# DC-DC_24V_To_5V0.net
KiCad netlist of a schematic drawn in Altium Designer
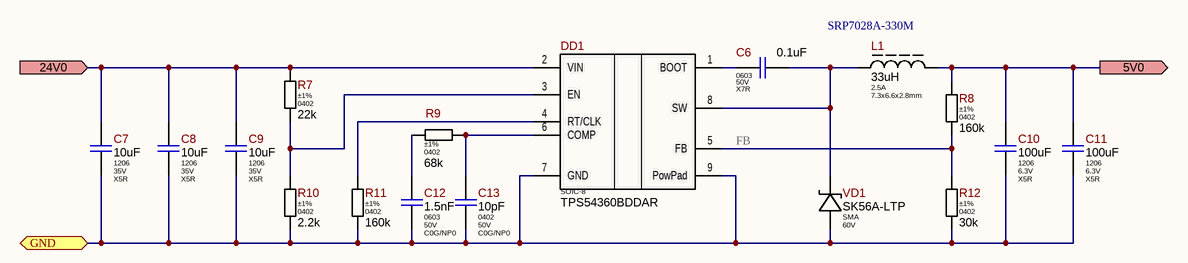
[diagram p0: DC-DC_24V_To_5V0.SchDoc]

(export (version "E")
  (design (tool "Eeschema 10.0.6"))
  (components
    (comp (ref "C6")
      (value "0.1uF")
      (footprint "C_CERAMIC_0603_MED")
      (description "100nF 50V X7R ±10% 0603 Ceramic Capacitor RoHS")
      (fields
        (field (name "PACKAGE") "0603")
        (field (name "VOLTAGE") "50V")
        (field (name "DIELECTRIC TYPE") "X7R")
        (field (name "PART NUMBER") "CL10B104KB8NNNC")
        (field (name "MANUFACTURER") "Samsung Electro-Mechanics")
      )
      (libsource (lib "EL.XXX.T01") (part "Capacitor-NonPolar"))
    )
    (comp (ref "C7")
      (value "10uF")
      (footprint "CAP-1206(3216)X85T15")
      (description "10uF 35V X5R ±10% 1206 Ceramic Capacitor RoHS")
      (fields
        (field (name "PACKAGE") "1206")
        (field (name "VOLTAGE") "35V")
        (field (name "DIELECTRIC TYPE") "X5R")
        (field (name "PART NUMBER") "GRM319R6YA106KA12D")
        (field (name "MANUFACTURER") "Murata Electronics")
      )
      (libsource (lib "EL.XXX.T01") (part "Capacitor-NonPolar"))
    )
    (comp (ref "C8")
      (value "10uF")
      (footprint "CAP-1206(3216)X85T15")
      (description "10uF 35V X5R ±10% 1206 Ceramic Capacitor RoHS")
      (fields
        (field (name "PACKAGE") "1206")
        (field (name "VOLTAGE") "35V")
        (field (name "DIELECTRIC TYPE") "X5R")
        (field (name "PART NUMBER") "GRM319R6YA106KA12D")
        (field (name "MANUFACTURER") "Murata Electronics")
      )
      (libsource (lib "EL.XXX.T01") (part "Capacitor-NonPolar"))
    )
    (comp (ref "C9")
      (value "10uF")
      (footprint "CAP-1206(3216)X85T15")
      (description "10uF 35V X5R ±10% 1206 Ceramic Capacitor RoHS")
      (fields
        (field (name "PACKAGE") "1206")
        (field (name "VOLTAGE") "35V")
        (field (name "DIELECTRIC TYPE") "X5R")
        (field (name "PART NUMBER") "GRM319R6YA106KA12D")
        (field (name "MANUFACTURER") "Murata Electronics")
      )
      (libsource (lib "EL.XXX.T01") (part "Capacitor-NonPolar"))
    )
    (comp (ref "C10")
      (value "100uF")
      (footprint "C_CERAMIC_1206_MED")
      (description "100uF 6.3V X5R ±20% 1206 Ceramic Capacitor RoHS")
      (fields
        (field (name "PACKAGE") "1206")
        (field (name "VOLTAGE") "6.3V")
        (field (name "DIELECTRIC TYPE") "X5R")
        (field (name "PART NUMBER") "CL31A107MQHNNNE")
        (field (name "MANUFACTURER") "Samsung Electro-Mechanics")
      )
      (libsource (lib "EL.XXX.T01") (part "Capacitor-NonPolar"))
    )
    (comp (ref "C11")
      (value "100uF")
      (footprint "C_CERAMIC_1206_MED")
      (description "100uF 6.3V X5R ±20% 1206 Ceramic Capacitor RoHS")
      (fields
        (field (name "PACKAGE") "1206")
        (field (name "VOLTAGE") "6.3V")
        (field (name "DIELECTRIC TYPE") "X5R")
        (field (name "PART NUMBER") "CL31A107MQHNNNE")
        (field (name "MANUFACTURER") "Samsung Electro-Mechanics")
      )
      (libsource (lib "EL.XXX.T01") (part "Capacitor-NonPolar"))
    )
    (comp (ref "C12")
      (value "1.5nF")
      (footprint "C_CERAMIC_0603_MED")
      (description "1.5nF 50V C0G(NP0) ±5% 0603 Ceramic Capacitor RoHS")
      (fields
        (field (name "PACKAGE") "0603")
        (field (name "VOLTAGE") "50V")
        (field (name "DIELECTRIC TYPE") "C0G/NP0")
        (field (name "PART NUMBER") "GRM1885C1H152JA01D")
        (field (name "MANUFACTURER") "Murata Electronics")
      )
      (libsource (lib "EL.XXX.T01") (part "Capacitor-NonPolar"))
    )
    (comp (ref "C13")
      (value "10pF")
      (footprint "C_CERAMIC_0402_MED")
      (description "10pF 50V C0G ±5% 0402 Ceramic Capacitor RoHS")
      (fields
        (field (name "PACKAGE") "0402")
        (field (name "VOLTAGE") "50V")
        (field (name "DIELECTRIC TYPE") "C0G/NP0")
        (field (name "PART NUMBER") "CL05C100JB5NNNC")
        (field (name "MANUFACTURER") "Samsung Electro-Mechanics")
      )
      (libsource (lib "EL.XXX.T01") (part "Capacitor-NonPolar"))
    )
    (comp (ref "DD1")
      (value "TPS54360BDDAR")
      (footprint "SOIC127P620X170_HS-9N")
      (description "60V Input, 3.5A, Step-Down DC/DC Converter With Eco-Mode, SOIC-8 EP")
      (fields
        (field (name "PACKAGE") "SOIC-8")
        (field (name "PART NUMBER") "TPS54360BDDAR")
        (field (name "MANUFACTURER") "Texas Instruments")
      )
      (libsource (lib "EL.XXX.T01") (part "TPS54360B"))
    )
    (comp (ref "L1")
      (value "33uH")
      (footprint "SRP7028A-Series")
      (description "33uH Shielded Wirewound Power Inductor 2.5A 240mOhm Max")
      (fields
        (field (name "CURRENT") "2.5A")
        (field (name "PACKAGE") "7.3x6.6x2.8mm")
        (field (name "PART NUMBER") "SRP7028A-330M")
        (field (name "TOLERANCE") "±20%")
        (field (name "MANUFACTURER") "Bourns Inc")
      )
      (libsource (lib "EL.XXX.T01") (part "Inductor-Ferrite-Fixed"))
    )
    (comp (ref "R7")
      (value "22k")
      (footprint "R_ANY_CHIP_0402_MED")
      (description "22 kOhms ±1% 1/16W 0402 Thick Film Resistor")
      (fields
        (field (name "TOLERANCE") "±1%")
        (field (name "PACKAGE") "0402")
        (field (name "PART NUMBER") "RC0402FR-0722KL")
        (field (name "MANUFACTURER") "Yageo")
      )
      (libsource (lib "EL.XXX.T01") (part "Resistor"))
    )
    (comp (ref "R8")
      (value "160k")
      (footprint "R_ANY_CHIP_0402_MED")
      (description "160 kOhms ±1% 1/16W 0402 Thick Film Resistor")
      (fields
        (field (name "TOLERANCE") "±1%")
        (field (name "PACKAGE") "0402")
        (field (name "PART NUMBER") "RC0402FR-07160KL")
        (field (name "MANUFACTURER") "Yageo")
      )
      (libsource (lib "EL.XXX.T01") (part "Resistor"))
    )
    (comp (ref "R9")
      (value "68k")
      (footprint "R_ANY_CHIP_0402_MED")
      (description "68 kOhms ±1% 1/16W 0402 Thick Film Resistor")
      (fields
        (field (name "TOLERANCE") "±1%")
        (field (name "PACKAGE") "0402")
        (field (name "PART NUMBER") "RC0402FR-0768KL")
        (field (name "MANUFACTURER") "Yageo")
      )
      (libsource (lib "EL.XXX.T01") (part "Resistor"))
    )
    (comp (ref "R10")
      (value "2.2k")
      (footprint "R_ANY_CHIP_0402_MED")
      (description "2.2 kOhms ±1% 1/16W 0402 Thick Film Resistor")
      (fields
        (field (name "TOLERANCE") "±1%")
        (field (name "PACKAGE") "0402")
        (field (name "PART NUMBER") "RC0402FR-072K2L")
        (field (name "MANUFACTURER") "Yageo")
      )
      (libsource (lib "EL.XXX.T01") (part "Resistor"))
    )
    (comp (ref "R11")
      (value "160k")
      (footprint "R_ANY_CHIP_0402_MED")
      (description "160 kOhms ±1% 1/16W 0402 Thick Film Resistor")
      (fields
        (field (name "TOLERANCE") "±1%")
        (field (name "PACKAGE") "0402")
        (field (name "PART NUMBER") "RC0402FR-07160KL")
        (field (name "MANUFACTURER") "Yageo")
      )
      (libsource (lib "EL.XXX.T01") (part "Resistor"))
    )
    (comp (ref "R12")
      (value "30k")
      (footprint "R_ANY_CHIP_0402_MED")
      (description "30 kOhms ±1% 1/16W 0402 Thick Film Resistor")
      (fields
        (field (name "TOLERANCE") "±1%")
        (field (name "PACKAGE") "0402")
        (field (name "PART NUMBER") "RC0402FR-0730KL")
        (field (name "MANUFACTURER") "Yageo")
      )
      (libsource (lib "EL.XXX.T01") (part "Resistor"))
    )
    (comp (ref "VD1")
      (value "SK56A-LTP")
      (footprint "SMA_MED")
      (description "Diode Schottky 60V 5A, SMA")
      (fields
        (field (name "PART NUMBER") "SK56A-LTP")
        (field (name "PACKAGE") "SMA")
        (field (name "VOLTAGE") "60V")
        (field (name "MANUFACTURER") "Micro Commercial Components")
      )
      (libsource (lib "EL.XXX.T01") (part "Diode-Schottky"))
    )
  )
  (nets
    (net (code "1") (name "/5V0") (class "Default")
      (node (ref "C10") (pin "1") (pinfunction "1_1") (pintype "passive"))
      (node (ref "C11") (pin "1") (pinfunction "1_1") (pintype "passive"))
      (node (ref "L1") (pin "2") (pintype "passive"))
      (node (ref "R8") (pin "1") (pintype "passive"))
    )
    (net (code "2") (name "/24V0") (class "Default")
      (node (ref "C7") (pin "1") (pinfunction "1_1") (pintype "passive"))
      (node (ref "C8") (pin "1") (pinfunction "1_1") (pintype "passive"))
      (node (ref "C9") (pin "1") (pinfunction "1_1") (pintype "passive"))
      (node (ref "DD1") (pin "2") (pinfunction "VIN_2") (pintype "passive"))
      (node (ref "R7") (pin "1") (pintype "passive"))
    )
    (net (code "3") (name "/FB") (class "Default")
      (node (ref "DD1") (pin "5") (pinfunction "FB_5") (pintype "passive"))
      (node (ref "R12") (pin "1") (pintype "passive"))
      (node (ref "R8") (pin "2") (pintype "passive"))
    )
    (net (code "4") (name "/GND") (class "Default")
      (node (ref "C10") (pin "2") (pinfunction "2_2") (pintype "passive"))
      (node (ref "C11") (pin "2") (pinfunction "2_2") (pintype "passive"))
      (node (ref "C12") (pin "1") (pinfunction "1_1") (pintype "passive"))
      (node (ref "C13") (pin "2") (pinfunction "2_2") (pintype "passive"))
      (node (ref "C7") (pin "2") (pinfunction "2_2") (pintype "passive"))
      (node (ref "C8") (pin "2") (pinfunction "2_2") (pintype "passive"))
      (node (ref "C9") (pin "2") (pinfunction "2_2") (pintype "passive"))
      (node (ref "DD1") (pin "7") (pinfunction "GND_7") (pintype "passive"))
      (node (ref "DD1") (pin "9") (pinfunction "PowPad_9") (pintype "passive"))
      (node (ref "R10") (pin "2") (pintype "passive"))
      (node (ref "R11") (pin "2") (pintype "passive"))
      (node (ref "R12") (pin "2") (pintype "passive"))
      (node (ref "VD1") (pin "AN") (pintype "passive"))
    )
    (net (code "5") (name "Net-(C12-Pad2)") (class "Default")
      (node (ref "C12") (pin "2") (pinfunction "2_2") (pintype "passive"))
      (node (ref "R9") (pin "2") (pintype "passive"))
    )
    (net (code "6") (name "Net-(DD1-BOOT)") (class "Default")
      (node (ref "C6") (pin "1") (pinfunction "1_1") (pintype "passive"))
      (node (ref "DD1") (pin "1") (pinfunction "BOOT_1") (pintype "passive"))
    )
    (net (code "7") (name "Net-(DD1-COMP)") (class "Default")
      (node (ref "C13") (pin "1") (pinfunction "1_1") (pintype "passive"))
      (node (ref "DD1") (pin "6") (pinfunction "COMP_6") (pintype "passive"))
      (node (ref "R9") (pin "1") (pintype "passive"))
    )
    (net (code "8") (name "Net-(DD1-EN)") (class "Default")
      (node (ref "DD1") (pin "3") (pinfunction "EN_3") (pintype "passive"))
      (node (ref "R10") (pin "1") (pintype "passive"))
      (node (ref "R7") (pin "2") (pintype "passive"))
    )
    (net (code "9") (name "Net-(DD1-RT{slash}CLK)") (class "Default")
      (node (ref "DD1") (pin "4") (pinfunction "RT/CLK_4") (pintype "passive"))
      (node (ref "R11") (pin "1") (pintype "passive"))
    )
    (net (code "10") (name "Net-(DD1-SW)") (class "Default")
      (node (ref "C6") (pin "2") (pinfunction "2_2") (pintype "passive"))
      (node (ref "DD1") (pin "8") (pinfunction "SW_8") (pintype "passive"))
      (node (ref "L1") (pin "1") (pintype "passive"))
      (node (ref "VD1") (pin "CA") (pintype "passive"))
    )
  )
)
